# pureDuino.net
KiCad netlist of a schematic drawn in EAGLE
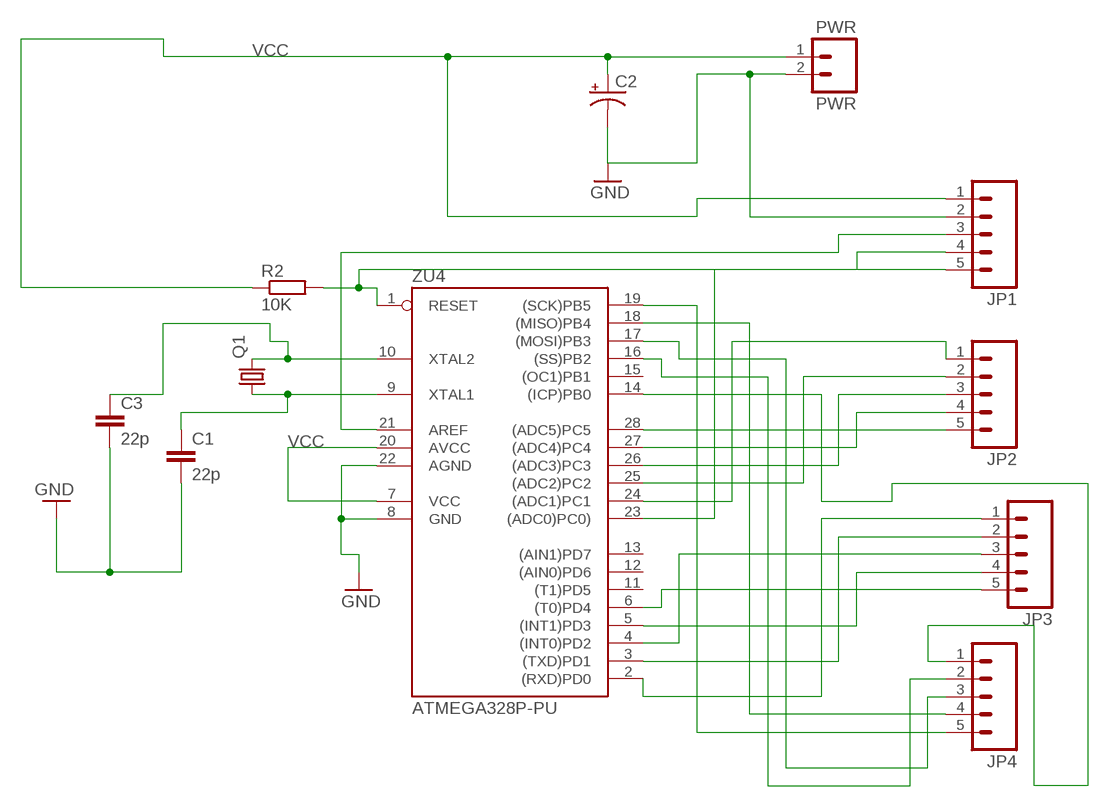
[diagram p0: schematic, sheet 1]

(export (version "E")
  (design (tool "Eeschema 10.0.6"))
  (components
    (comp (ref "C1")
      (value "22p")
      (footprint "eagle-import:C050-025X075")
      (libsource (lib "eagle-import") (part "C-EU050-025X075"))
    )
    (comp (ref "C2")
      (value "CAP_POLPTH1")
      (footprint "eagle-import:CPOL-RADIAL-100UF-25V")
      (libsource (lib "eagle-import") (part "CAP_POLPTH1"))
    )
    (comp (ref "C3")
      (value "22p")
      (footprint "eagle-import:C050-025X075")
      (libsource (lib "eagle-import") (part "C-EU050-025X075"))
    )
    (comp (ref "JP1")
      (value "M05PTH")
      (footprint "eagle-import:1X05")
      (libsource (lib "eagle-import") (part "M05PTH"))
    )
    (comp (ref "JP2")
      (value "M05PTH")
      (footprint "eagle-import:1X05")
      (libsource (lib "eagle-import") (part "M05PTH"))
    )
    (comp (ref "JP3")
      (value "M05PTH")
      (footprint "eagle-import:1X05")
      (libsource (lib "eagle-import") (part "M05PTH"))
    )
    (comp (ref "JP4")
      (value "M05PTH")
      (footprint "eagle-import:1X05")
      (libsource (lib "eagle-import") (part "M05PTH"))
    )
    (comp (ref "PWR")
      (value "PWR")
      (footprint "eagle-import:1X02")
      (libsource (lib "eagle-import") (part "M02PTH"))
    )
    (comp (ref "Q1")
      (value "CRYSTALHC49S")
      (footprint "eagle-import:HC49_S")
      (libsource (lib "eagle-import") (part "CRYSTALHC49S"))
    )
    (comp (ref "R2")
      (value "10K")
      (footprint "eagle-import:0207_7")
      (libsource (lib "eagle-import") (part "R-EU_0207/7"))
    )
    (comp (ref "ZU4")
      (value "ATMEGA328P-PU")
      (footprint "eagle-import:DIL28-3")
      (libsource (lib "eagle-import") (part "ATMEGA328P-PU"))
    )
  )
  (nets
    (net (code "1") (name "/VCC") (class "Default")
      (node (ref "C2") (pin "1") (pinfunction "+_1") (pintype "passive"))
      (node (ref "JP1") (pin "1") (pinfunction "1_1") (pintype "passive"))
      (node (ref "PWR") (pin "1") (pinfunction "1_1") (pintype "passive"))
      (node (ref "R2") (pin "1") (pinfunction "1_1") (pintype "passive"))
      (node (ref "ZU4") (pin "20") (pinfunction "AVCC_20") (pintype "power_in"))
      (node (ref "ZU4") (pin "7") (pinfunction "VCC_7") (pintype "power_in"))
    )
    (net (code "2") (name "GND") (class "Default")
      (node (ref "C1") (pin "2") (pinfunction "2_2") (pintype "passive"))
      (node (ref "C2") (pin "2") (pinfunction "-_2") (pintype "passive"))
      (node (ref "C3") (pin "2") (pinfunction "2_2") (pintype "passive"))
      (node (ref "JP1") (pin "2") (pinfunction "2_2") (pintype "passive"))
      (node (ref "PWR") (pin "2") (pinfunction "2_2") (pintype "passive"))
      (node (ref "ZU4") (pin "22") (pinfunction "AGND_22") (pintype "power_in"))
      (node (ref "ZU4") (pin "8") (pinfunction "GND_8") (pintype "power_in"))
    )
    (net (code "3") (name "Net-(ZU4-(ADC0)PC0))") (class "Default")
      (node (ref "JP1") (pin "5") (pinfunction "5_5") (pintype "passive"))
      (node (ref "ZU4") (pin "23") (pinfunction "(ADC0)PC0)_23") (pintype "bidirectional"))
    )
    (net (code "4") (name "Net-(ZU4-(ADC1)PC1)") (class "Default")
      (node (ref "JP2") (pin "1") (pinfunction "1_1") (pintype "passive"))
      (node (ref "ZU4") (pin "24") (pinfunction "(ADC1)PC1_24") (pintype "bidirectional"))
    )
    (net (code "5") (name "Net-(ZU4-(ADC2)PC2)") (class "Default")
      (node (ref "JP2") (pin "2") (pinfunction "2_2") (pintype "passive"))
      (node (ref "ZU4") (pin "25") (pinfunction "(ADC2)PC2_25") (pintype "bidirectional"))
    )
    (net (code "6") (name "Net-(ZU4-(ADC3)PC3)") (class "Default")
      (node (ref "JP2") (pin "3") (pinfunction "3_3") (pintype "passive"))
      (node (ref "ZU4") (pin "26") (pinfunction "(ADC3)PC3_26") (pintype "bidirectional"))
    )
    (net (code "7") (name "Net-(ZU4-(ADC4)PC4)") (class "Default")
      (node (ref "JP2") (pin "4") (pinfunction "4_4") (pintype "passive"))
      (node (ref "ZU4") (pin "27") (pinfunction "(ADC4)PC4_27") (pintype "bidirectional"))
    )
    (net (code "8") (name "Net-(ZU4-(ADC5)PC5)") (class "Default")
      (node (ref "JP2") (pin "5") (pinfunction "5_5") (pintype "passive"))
      (node (ref "ZU4") (pin "28") (pinfunction "(ADC5)PC5_28") (pintype "bidirectional"))
    )
    (net (code "9") (name "Net-(ZU4-(ICP)PB0)") (class "Default")
      (node (ref "JP4") (pin "1") (pinfunction "1_1") (pintype "passive"))
      (node (ref "ZU4") (pin "14") (pinfunction "(ICP)PB0_14") (pintype "bidirectional"))
    )
    (net (code "10") (name "Net-(ZU4-(INT0)PD2)") (class "Default")
      (node (ref "JP3") (pin "3") (pinfunction "3_3") (pintype "passive"))
      (node (ref "ZU4") (pin "4") (pinfunction "(INT0)PD2_4") (pintype "bidirectional"))
    )
    (net (code "11") (name "Net-(ZU4-(INT1)PD3)") (class "Default")
      (node (ref "JP3") (pin "4") (pinfunction "4_4") (pintype "passive"))
      (node (ref "ZU4") (pin "5") (pinfunction "(INT1)PD3_5") (pintype "bidirectional"))
    )
    (net (code "12") (name "Net-(ZU4-(MISO)PB4)") (class "Default")
      (node (ref "JP4") (pin "4") (pinfunction "4_4") (pintype "passive"))
      (node (ref "ZU4") (pin "18") (pinfunction "(MISO)PB4_18") (pintype "bidirectional"))
    )
    (net (code "13") (name "Net-(ZU4-(MOSI)PB3)") (class "Default")
      (node (ref "JP4") (pin "3") (pinfunction "3_3") (pintype "passive"))
      (node (ref "ZU4") (pin "17") (pinfunction "(MOSI)PB3_17") (pintype "bidirectional"))
    )
    (net (code "14") (name "Net-(ZU4-(RXD)PD0)") (class "Default")
      (node (ref "JP3") (pin "1") (pinfunction "1_1") (pintype "passive"))
      (node (ref "ZU4") (pin "2") (pinfunction "(RXD)PD0_2") (pintype "bidirectional"))
    )
    (net (code "15") (name "Net-(ZU4-(SCK)PB5)") (class "Default")
      (node (ref "JP4") (pin "5") (pinfunction "5_5") (pintype "passive"))
      (node (ref "ZU4") (pin "19") (pinfunction "(SCK)PB5_19") (pintype "bidirectional"))
    )
    (net (code "16") (name "Net-(ZU4-(SS)PB2)") (class "Default")
      (node (ref "JP4") (pin "2") (pinfunction "2_2") (pintype "passive"))
      (node (ref "ZU4") (pin "16") (pinfunction "(SS)PB2_16") (pintype "bidirectional"))
    )
    (net (code "17") (name "Net-(ZU4-(T0)PD4)") (class "Default")
      (node (ref "JP3") (pin "5") (pinfunction "5_5") (pintype "passive"))
      (node (ref "ZU4") (pin "6") (pinfunction "(T0)PD4_6") (pintype "bidirectional"))
    )
    (net (code "18") (name "Net-(ZU4-(TXD)PD1)") (class "Default")
      (node (ref "JP3") (pin "2") (pinfunction "2_2") (pintype "passive"))
      (node (ref "ZU4") (pin "3") (pinfunction "(TXD)PD1_3") (pintype "bidirectional"))
    )
    (net (code "19") (name "Net-(ZU4-AREF)") (class "Default")
      (node (ref "JP1") (pin "3") (pinfunction "3_3") (pintype "passive"))
      (node (ref "ZU4") (pin "21") (pinfunction "AREF_21") (pintype "passive"))
    )
    (net (code "20") (name "Net-(ZU4-RESET)") (class "Default")
      (node (ref "JP1") (pin "4") (pinfunction "4_4") (pintype "passive"))
      (node (ref "R2") (pin "2") (pinfunction "2_2") (pintype "passive"))
      (node (ref "ZU4") (pin "1") (pinfunction "RESET_1") (pintype "input"))
    )
    (net (code "21") (name "Net-(ZU4-XTAL1)") (class "Default")
      (node (ref "C1") (pin "1") (pinfunction "1_1") (pintype "passive"))
      (node (ref "Q1") (pin "1") (pinfunction "1_1") (pintype "passive"))
      (node (ref "ZU4") (pin "9") (pinfunction "XTAL1_9") (pintype "bidirectional"))
    )
    (net (code "22") (name "Net-(ZU4-XTAL2)") (class "Default")
      (node (ref "C3") (pin "1") (pinfunction "1_1") (pintype "passive"))
      (node (ref "Q1") (pin "2") (pinfunction "2_2") (pintype "passive"))
      (node (ref "ZU4") (pin "10") (pinfunction "XTAL2_10") (pintype "bidirectional"))
    )
    (net (code "23") (name "unconnected-(ZU4-(AIN0)PD6-Pad12)") (class "Default")
      (node (ref "ZU4") (pin "12") (pinfunction "(AIN0)PD6_12") (pintype "bidirectional"))
    )
    (net (code "24") (name "unconnected-(ZU4-(AIN1)PD7-Pad13)") (class "Default")
      (node (ref "ZU4") (pin "13") (pinfunction "(AIN1)PD7_13") (pintype "bidirectional"))
    )
    (net (code "25") (name "unconnected-(ZU4-(OC1)PB1-Pad15)") (class "Default")
      (node (ref "ZU4") (pin "15") (pinfunction "(OC1)PB1_15") (pintype "bidirectional"))
    )
    (net (code "26") (name "unconnected-(ZU4-(T1)PD5-Pad11)") (class "Default")
      (node (ref "ZU4") (pin "11") (pinfunction "(T1)PD5_11") (pintype "bidirectional"))
    )
  )
)
